# jarpysdr.net
KiCad netlist of a schematic drawn in EAGLE
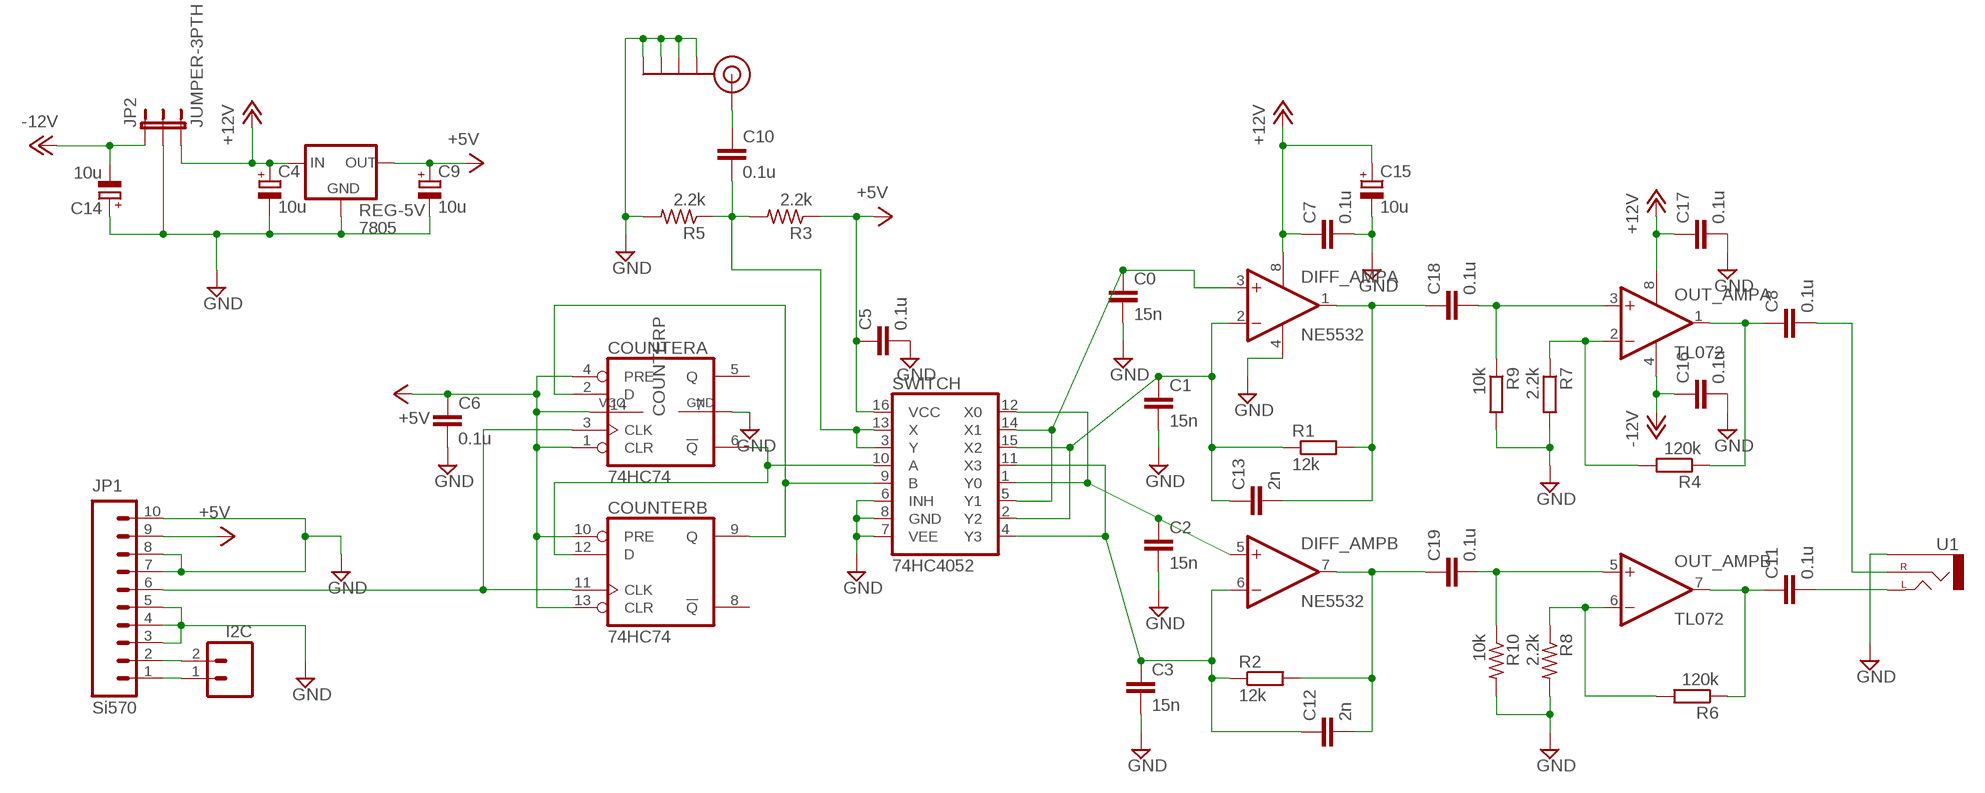
[diagram p0: schematic, sheet 1]

(export (version "E")
  (design (tool "Eeschema 10.0.6"))
  (components
    (comp (ref "ANTENNA")
      (value "SMA_EDGE")
      (footprint "eagle-import:SMA-EDGE")
      (libsource (lib "eagle-import") (part "SMA_EDGE"))
    )
    (comp (ref "C0")
      (value "15n")
      (footprint "eagle-import:C025-024X044")
      (libsource (lib "eagle-import") (part "C-EU025-024X044"))
    )
    (comp (ref "C1")
      (value "15n")
      (footprint "eagle-import:C025-024X044")
      (libsource (lib "eagle-import") (part "C-EU025-024X044"))
    )
    (comp (ref "C2")
      (value "15n")
      (footprint "eagle-import:C025-024X044")
      (libsource (lib "eagle-import") (part "C-EU025-024X044"))
    )
    (comp (ref "C3")
      (value "15n")
      (footprint "eagle-import:C025-024X044")
      (libsource (lib "eagle-import") (part "C-EU025-024X044"))
    )
    (comp (ref "C4")
      (value "10u")
      (footprint "eagle-import:E2,5-6")
      (libsource (lib "eagle-import") (part "CPOL-EUE2.5-6"))
    )
    (comp (ref "C5")
      (value "0.1u")
      (footprint "eagle-import:C025-025X050")
      (libsource (lib "eagle-import") (part "C-EU025-025X050"))
    )
    (comp (ref "C6")
      (value "0.1u")
      (footprint "eagle-import:C025-025X050")
      (libsource (lib "eagle-import") (part "C-EU025-025X050"))
    )
    (comp (ref "C7")
      (value "0.1u")
      (footprint "eagle-import:C025-025X050")
      (libsource (lib "eagle-import") (part "C-EU025-025X050"))
    )
    (comp (ref "C8")
      (value "0.1u")
      (footprint "eagle-import:C050-025X075")
      (libsource (lib "eagle-import") (part "C-EU050-025X075"))
    )
    (comp (ref "C9")
      (value "10u")
      (footprint "eagle-import:E2,5-6")
      (libsource (lib "eagle-import") (part "CPOL-EUE2.5-6"))
    )
    (comp (ref "C10")
      (value "0.1u")
      (footprint "eagle-import:C025-024X044")
      (libsource (lib "eagle-import") (part "C-EU025-024X044"))
    )
    (comp (ref "C11")
      (value "0.1u")
      (footprint "eagle-import:C050-025X075")
      (libsource (lib "eagle-import") (part "C-EU050-025X075"))
    )
    (comp (ref "C12")
      (value "2n")
      (footprint "eagle-import:C025-024X044")
      (libsource (lib "eagle-import") (part "C-EU025-024X044"))
    )
    (comp (ref "C13")
      (value "2n")
      (footprint "eagle-import:C025-024X044")
      (libsource (lib "eagle-import") (part "C-EU025-024X044"))
    )
    (comp (ref "C14")
      (value "10u")
      (footprint "eagle-import:E2,5-6")
      (libsource (lib "eagle-import") (part "CPOL-EUE2.5-6"))
    )
    (comp (ref "C15")
      (value "10u")
      (footprint "eagle-import:E2,5-6")
      (libsource (lib "eagle-import") (part "CPOL-EUE2.5-6"))
    )
    (comp (ref "C16")
      (value "0.1u")
      (footprint "eagle-import:C025-025X050")
      (libsource (lib "eagle-import") (part "C-EU025-025X050"))
    )
    (comp (ref "C17")
      (value "0.1u")
      (footprint "eagle-import:C025-025X050")
      (libsource (lib "eagle-import") (part "C-EU025-025X050"))
    )
    (comp (ref "C18")
      (value "0.1u")
      (footprint "eagle-import:C050-025X075")
      (libsource (lib "eagle-import") (part "C-EU050-025X075"))
    )
    (comp (ref "C19")
      (value "0.1u")
      (footprint "eagle-import:C050-025X075")
      (libsource (lib "eagle-import") (part "C-EU050-025X075"))
    )
    (comp (ref "COUNTER")
      (value "74HC74")
      (footprint "eagle-import:DIL14")
      (libsource (lib "eagle-import") (part "7474NHC"))
    )
    (comp (ref "DIFF_AMP")
      (value "NE5532")
      (footprint "eagle-import:DIL08")
      (libsource (lib "eagle-import") (part "NE5532N"))
    )
    (comp (ref "I2C")
      (value "M02PTH")
      (footprint "eagle-import:1X02")
      (libsource (lib "eagle-import") (part "M02PTH"))
    )
    (comp (ref "JP1")
      (value "Si570")
      (footprint "eagle-import:1X10")
      (libsource (lib "eagle-import") (part "M10{dblquote}"))
    )
    (comp (ref "JP2")
      (value "JUMPER-3PTH")
      (footprint "eagle-import:1X03")
      (libsource (lib "eagle-import") (part "JUMPER-3PTH"))
    )
    (comp (ref "OUT_AMP")
      (value "TL072")
      (footprint "eagle-import:DIL08")
      (libsource (lib "eagle-import") (part "TL072P"))
    )
    (comp (ref "R1")
      (value "12k")
      (footprint "eagle-import:0204_7")
      (libsource (lib "eagle-import") (part "R-EU_0204/7"))
    )
    (comp (ref "R2")
      (value "12k")
      (footprint "eagle-import:0204_7")
      (libsource (lib "eagle-import") (part "R-EU_0204/7"))
    )
    (comp (ref "R3")
      (value "2.2k")
      (footprint "eagle-import:0204_7")
      (libsource (lib "eagle-import") (part "R-US_0204/7"))
    )
    (comp (ref "R4")
      (value "120k")
      (footprint "eagle-import:0204_7")
      (libsource (lib "eagle-import") (part "R-EU_0204/7"))
    )
    (comp (ref "R5")
      (value "2.2k")
      (footprint "eagle-import:0204_7")
      (libsource (lib "eagle-import") (part "R-US_0204/7"))
    )
    (comp (ref "R6")
      (value "120k")
      (footprint "eagle-import:0204_7")
      (libsource (lib "eagle-import") (part "R-EU_0204/7"))
    )
    (comp (ref "R7")
      (value "2.2k")
      (footprint "eagle-import:0204_7")
      (libsource (lib "eagle-import") (part "R-EU_0204/7"))
    )
    (comp (ref "R8")
      (value "2.2k")
      (footprint "eagle-import:0204_7")
      (libsource (lib "eagle-import") (part "R-US_0204/7"))
    )
    (comp (ref "R9")
      (value "10k")
      (footprint "eagle-import:0204_7")
      (libsource (lib "eagle-import") (part "R-EU_0204/7"))
    )
    (comp (ref "R10")
      (value "10k")
      (footprint "eagle-import:0204_7")
      (libsource (lib "eagle-import") (part "R-US_0204/7"))
    )
    (comp (ref "REG-5V")
      (value "7805")
      (footprint "eagle-import:78XXS")
      (libsource (lib "eagle-import") (part "78XXS"))
    )
    (comp (ref "SWITCH")
      (value "74HC4052")
      (footprint "eagle-import:DIL16")
      (libsource (lib "eagle-import") (part "74HC4052DIP"))
    )
    (comp (ref "U1")
      (value "AUDIO-JACKPTH")
      (footprint "eagle-import:AUDIO-JACK")
      (libsource (lib "eagle-import") (part "AUDIO-JACKPTH"))
    )
  )
  (nets
    (net (code "1") (name "+5V") (class "Default")
      (node (ref "C5") (pin "1") (pinfunction "1_1") (pintype "passive"))
      (node (ref "C6") (pin "1") (pinfunction "1_1") (pintype "passive"))
      (node (ref "C9") (pin "+") (pinfunction "+_+") (pintype "passive"))
      (node (ref "COUNTER") (pin "1") (pinfunction "CLR_1") (pintype "input"))
      (node (ref "COUNTER") (pin "10") (pinfunction "PRE_10") (pintype "input"))
      (node (ref "COUNTER") (pin "13") (pinfunction "CLR_13") (pintype "input"))
      (node (ref "COUNTER") (pin "14") (pinfunction "VCC_14") (pintype "power_in"))
      (node (ref "COUNTER") (pin "4") (pinfunction "PRE_4") (pintype "input"))
      (node (ref "JP1") (pin "9") (pinfunction "9_9") (pintype "passive"))
      (node (ref "R3") (pin "1") (pinfunction "1_1") (pintype "passive"))
      (node (ref "REG-5V") (pin "OUT") (pinfunction "OUT_OUT") (pintype "passive"))
      (node (ref "SWITCH") (pin "16") (pinfunction "VCC_16") (pintype "power_in"))
    )
    (net (code "2") (name "+12V") (class "Default")
      (node (ref "C15") (pin "+") (pinfunction "+_+") (pintype "passive"))
      (node (ref "C17") (pin "1") (pinfunction "1_1") (pintype "passive"))
      (node (ref "C4") (pin "+") (pinfunction "+_+") (pintype "passive"))
      (node (ref "C7") (pin "1") (pinfunction "1_1") (pintype "passive"))
      (node (ref "DIFF_AMP") (pin "8") (pinfunction "V+_8") (pintype "power_in"))
      (node (ref "JP2") (pin "3") (pinfunction "3_3") (pintype "passive"))
      (node (ref "OUT_AMP") (pin "8") (pinfunction "V+_8") (pintype "power_in"))
      (node (ref "REG-5V") (pin "IN") (pinfunction "IN_IN") (pintype "input"))
    )
    (net (code "3") (name "-12V") (class "Default")
      (node (ref "C14") (pin "-") (pinfunction "-_-") (pintype "passive"))
      (node (ref "C16") (pin "1") (pinfunction "1_1") (pintype "passive"))
      (node (ref "JP2") (pin "1") (pinfunction "1_1") (pintype "passive"))
      (node (ref "OUT_AMP") (pin "4") (pinfunction "V-_4") (pintype "power_in"))
    )
    (net (code "4") (name "GND") (class "Default")
      (node (ref "ANTENNA") (pin "GND@0") (pinfunction "GND_GND@0") (pintype "bidirectional"))
      (node (ref "ANTENNA") (pin "GND@1") (pinfunction "GND_GND@1") (pintype "bidirectional"))
      (node (ref "ANTENNA") (pin "GND@2") (pinfunction "GND_GND@2") (pintype "bidirectional"))
      (node (ref "ANTENNA") (pin "GND@3") (pinfunction "GND_GND@3") (pintype "bidirectional"))
      (node (ref "C0") (pin "2") (pinfunction "2_2") (pintype "passive"))
      (node (ref "C1") (pin "2") (pinfunction "2_2") (pintype "passive"))
      (node (ref "C14") (pin "+") (pinfunction "+_+") (pintype "passive"))
      (node (ref "C15") (pin "-") (pinfunction "-_-") (pintype "passive"))
      (node (ref "C16") (pin "2") (pinfunction "2_2") (pintype "passive"))
      (node (ref "C17") (pin "2") (pinfunction "2_2") (pintype "passive"))
      (node (ref "C2") (pin "2") (pinfunction "2_2") (pintype "passive"))
      (node (ref "C3") (pin "2") (pinfunction "2_2") (pintype "passive"))
      (node (ref "C4") (pin "-") (pinfunction "-_-") (pintype "passive"))
      (node (ref "C5") (pin "2") (pinfunction "2_2") (pintype "passive"))
      (node (ref "C6") (pin "2") (pinfunction "2_2") (pintype "passive"))
      (node (ref "C7") (pin "2") (pinfunction "2_2") (pintype "passive"))
      (node (ref "C9") (pin "-") (pinfunction "-_-") (pintype "passive"))
      (node (ref "COUNTER") (pin "7") (pinfunction "GND_7") (pintype "power_in"))
      (node (ref "DIFF_AMP") (pin "4") (pinfunction "V-_4") (pintype "power_in"))
      (node (ref "JP1") (pin "10") (pinfunction "10_10") (pintype "passive"))
      (node (ref "JP1") (pin "3") (pinfunction "3_3") (pintype "passive"))
      (node (ref "JP1") (pin "4") (pinfunction "4_4") (pintype "passive"))
      (node (ref "JP1") (pin "5") (pinfunction "5_5") (pintype "passive"))
      (node (ref "JP1") (pin "7") (pinfunction "7_7") (pintype "passive"))
      (node (ref "JP1") (pin "8") (pinfunction "8_8") (pintype "passive"))
      (node (ref "JP2") (pin "2") (pinfunction "2_2") (pintype "passive"))
      (node (ref "R10") (pin "2") (pinfunction "2_2") (pintype "passive"))
      (node (ref "R5") (pin "2") (pinfunction "2_2") (pintype "passive"))
      (node (ref "R7") (pin "2") (pinfunction "2_2") (pintype "passive"))
      (node (ref "R8") (pin "2") (pinfunction "2_2") (pintype "passive"))
      (node (ref "R9") (pin "2") (pinfunction "2_2") (pintype "passive"))
      (node (ref "REG-5V") (pin "GND") (pinfunction "GND_GND") (pintype "input"))
      (node (ref "SWITCH") (pin "6") (pinfunction "INH_6") (pintype "input"))
      (node (ref "SWITCH") (pin "7") (pinfunction "VEE_7") (pintype "power_in"))
      (node (ref "SWITCH") (pin "8") (pinfunction "GND_8") (pintype "power_in"))
      (node (ref "U1") (pin "SLEEVE") (pinfunction "SLEEVE_SLEEVE") (pintype "bidirectional"))
    )
    (net (code "5") (name "Net-(ANTENNA-SIGNAL)") (class "Default")
      (node (ref "ANTENNA") (pin "SIG") (pinfunction "SIGNAL_SIG") (pintype "bidirectional"))
      (node (ref "C10") (pin "1") (pinfunction "1_1") (pintype "passive"))
    )
    (net (code "6") (name "Net-(COUNTERA-CLK)") (class "Default")
      (node (ref "COUNTER") (pin "11") (pinfunction "CLK_11") (pintype "input"))
      (node (ref "COUNTER") (pin "3") (pinfunction "CLK_3") (pintype "input"))
      (node (ref "JP1") (pin "6") (pinfunction "6_6") (pintype "passive"))
    )
    (net (code "7") (name "Net-(COUNTERA-D)") (class "Default")
      (node (ref "COUNTER") (pin "2") (pinfunction "D_2") (pintype "input"))
      (node (ref "COUNTER") (pin "9") (pinfunction "Q_9") (pintype "output"))
      (node (ref "SWITCH") (pin "9") (pinfunction "B_9") (pintype "input"))
    )
    (net (code "8") (name "Net-(COUNTERA-~{Q})") (class "Default")
      (node (ref "COUNTER") (pin "12") (pinfunction "D_12") (pintype "input"))
      (node (ref "COUNTER") (pin "6") (pinfunction "~{Q}_6") (pintype "output"))
      (node (ref "SWITCH") (pin "10") (pinfunction "A_10") (pintype "input"))
    )
    (net (code "9") (name "Net-(DIFF_AMPA-+IN)") (class "Default")
      (node (ref "C0") (pin "1") (pinfunction "1_1") (pintype "passive"))
      (node (ref "DIFF_AMP") (pin "3") (pinfunction "+IN_3") (pintype "input"))
      (node (ref "SWITCH") (pin "14") (pinfunction "X1_14") (pintype "bidirectional"))
      (node (ref "SWITCH") (pin "5") (pinfunction "Y1_5") (pintype "bidirectional"))
    )
    (net (code "10") (name "Net-(DIFF_AMPA--IN)") (class "Default")
      (node (ref "C1") (pin "1") (pinfunction "1_1") (pintype "passive"))
      (node (ref "C13") (pin "1") (pinfunction "1_1") (pintype "passive"))
      (node (ref "DIFF_AMP") (pin "2") (pinfunction "-IN_2") (pintype "input"))
      (node (ref "R1") (pin "1") (pinfunction "1_1") (pintype "passive"))
      (node (ref "SWITCH") (pin "15") (pinfunction "X2_15") (pintype "bidirectional"))
      (node (ref "SWITCH") (pin "2") (pinfunction "Y2_2") (pintype "bidirectional"))
    )
    (net (code "11") (name "Net-(DIFF_AMPA-OUT)") (class "Default")
      (node (ref "C13") (pin "2") (pinfunction "2_2") (pintype "passive"))
      (node (ref "C18") (pin "1") (pinfunction "1_1") (pintype "passive"))
      (node (ref "DIFF_AMP") (pin "1") (pinfunction "OUT_1") (pintype "output"))
      (node (ref "R1") (pin "2") (pinfunction "2_2") (pintype "passive"))
    )
    (net (code "12") (name "Net-(DIFF_AMPB-+IN)") (class "Default")
      (node (ref "C2") (pin "1") (pinfunction "1_1") (pintype "passive"))
      (node (ref "DIFF_AMP") (pin "5") (pinfunction "+IN_5") (pintype "input"))
      (node (ref "SWITCH") (pin "1") (pinfunction "Y0_1") (pintype "bidirectional"))
      (node (ref "SWITCH") (pin "12") (pinfunction "X0_12") (pintype "bidirectional"))
    )
    (net (code "13") (name "Net-(DIFF_AMPB--IN)") (class "Default")
      (node (ref "C12") (pin "1") (pinfunction "1_1") (pintype "passive"))
      (node (ref "C3") (pin "1") (pinfunction "1_1") (pintype "passive"))
      (node (ref "DIFF_AMP") (pin "6") (pinfunction "-IN_6") (pintype "input"))
      (node (ref "R2") (pin "1") (pinfunction "1_1") (pintype "passive"))
      (node (ref "SWITCH") (pin "11") (pinfunction "X3_11") (pintype "bidirectional"))
      (node (ref "SWITCH") (pin "4") (pinfunction "Y3_4") (pintype "bidirectional"))
    )
    (net (code "14") (name "Net-(DIFF_AMPB-OUT)") (class "Default")
      (node (ref "C12") (pin "2") (pinfunction "2_2") (pintype "passive"))
      (node (ref "C19") (pin "1") (pinfunction "1_1") (pintype "passive"))
      (node (ref "DIFF_AMP") (pin "7") (pinfunction "OUT_7") (pintype "output"))
      (node (ref "R2") (pin "2") (pinfunction "2_2") (pintype "passive"))
    )
    (net (code "15") (name "Net-(I2C-Pad1)") (class "Default")
      (node (ref "I2C") (pin "1") (pinfunction "1_1") (pintype "passive"))
      (node (ref "JP1") (pin "1") (pinfunction "1_1") (pintype "passive"))
    )
    (net (code "16") (name "Net-(I2C-Pad2)") (class "Default")
      (node (ref "I2C") (pin "2") (pinfunction "2_2") (pintype "passive"))
      (node (ref "JP1") (pin "2") (pinfunction "2_2") (pintype "passive"))
    )
    (net (code "17") (name "Net-(OUT_AMPA-+IN)") (class "Default")
      (node (ref "C18") (pin "2") (pinfunction "2_2") (pintype "passive"))
      (node (ref "OUT_AMP") (pin "3") (pinfunction "+IN_3") (pintype "input"))
      (node (ref "R9") (pin "1") (pinfunction "1_1") (pintype "passive"))
    )
    (net (code "18") (name "Net-(OUT_AMPA--IN)") (class "Default")
      (node (ref "OUT_AMP") (pin "2") (pinfunction "-IN_2") (pintype "input"))
      (node (ref "R4") (pin "2") (pinfunction "2_2") (pintype "passive"))
      (node (ref "R7") (pin "1") (pinfunction "1_1") (pintype "passive"))
    )
    (net (code "19") (name "Net-(OUT_AMPA-OUT)") (class "Default")
      (node (ref "C8") (pin "1") (pinfunction "1_1") (pintype "passive"))
      (node (ref "OUT_AMP") (pin "1") (pinfunction "OUT_1") (pintype "output"))
      (node (ref "R4") (pin "1") (pinfunction "1_1") (pintype "passive"))
    )
    (net (code "20") (name "Net-(OUT_AMPB-+IN)") (class "Default")
      (node (ref "C19") (pin "2") (pinfunction "2_2") (pintype "passive"))
      (node (ref "OUT_AMP") (pin "5") (pinfunction "+IN_5") (pintype "input"))
      (node (ref "R10") (pin "1") (pinfunction "1_1") (pintype "passive"))
    )
    (net (code "21") (name "Net-(OUT_AMPB--IN)") (class "Default")
      (node (ref "OUT_AMP") (pin "6") (pinfunction "-IN_6") (pintype "input"))
      (node (ref "R6") (pin "2") (pinfunction "2_2") (pintype "passive"))
      (node (ref "R8") (pin "1") (pinfunction "1_1") (pintype "passive"))
    )
    (net (code "22") (name "Net-(OUT_AMPB-OUT)") (class "Default")
      (node (ref "C11") (pin "1") (pinfunction "1_1") (pintype "passive"))
      (node (ref "OUT_AMP") (pin "7") (pinfunction "OUT_7") (pintype "output"))
      (node (ref "R6") (pin "1") (pinfunction "1_1") (pintype "passive"))
    )
    (net (code "23") (name "Net-(SWITCH-X)") (class "Default")
      (node (ref "C10") (pin "2") (pinfunction "2_2") (pintype "passive"))
      (node (ref "R3") (pin "2") (pinfunction "2_2") (pintype "passive"))
      (node (ref "R5") (pin "1") (pinfunction "1_1") (pintype "passive"))
      (node (ref "SWITCH") (pin "13") (pinfunction "X_13") (pintype "bidirectional"))
      (node (ref "SWITCH") (pin "3") (pinfunction "Y_3") (pintype "bidirectional"))
    )
    (net (code "24") (name "Net-(U1-LEFT)") (class "Default")
      (node (ref "C11") (pin "2") (pinfunction "2_2") (pintype "passive"))
      (node (ref "U1") (pin "TIP") (pinfunction "LEFT_TIP") (pintype "bidirectional"))
    )
    (net (code "25") (name "Net-(U1-RIGHT)") (class "Default")
      (node (ref "C8") (pin "2") (pinfunction "2_2") (pintype "passive"))
      (node (ref "U1") (pin "RING") (pinfunction "RIGHT_RING") (pintype "bidirectional"))
    )
    (net (code "26") (name "unconnected-(COUNTERA-Q-Pad5)") (class "Default")
      (node (ref "COUNTER") (pin "5") (pinfunction "Q_5") (pintype "output"))
    )
    (net (code "27") (name "unconnected-(COUNTERB-~{Q}-Pad8)") (class "Default")
      (node (ref "COUNTER") (pin "8") (pinfunction "~{Q}_8") (pintype "output"))
    )
  )
)
